# AudioMega_v101.net
KiCad netlist of a schematic drawn in EAGLE
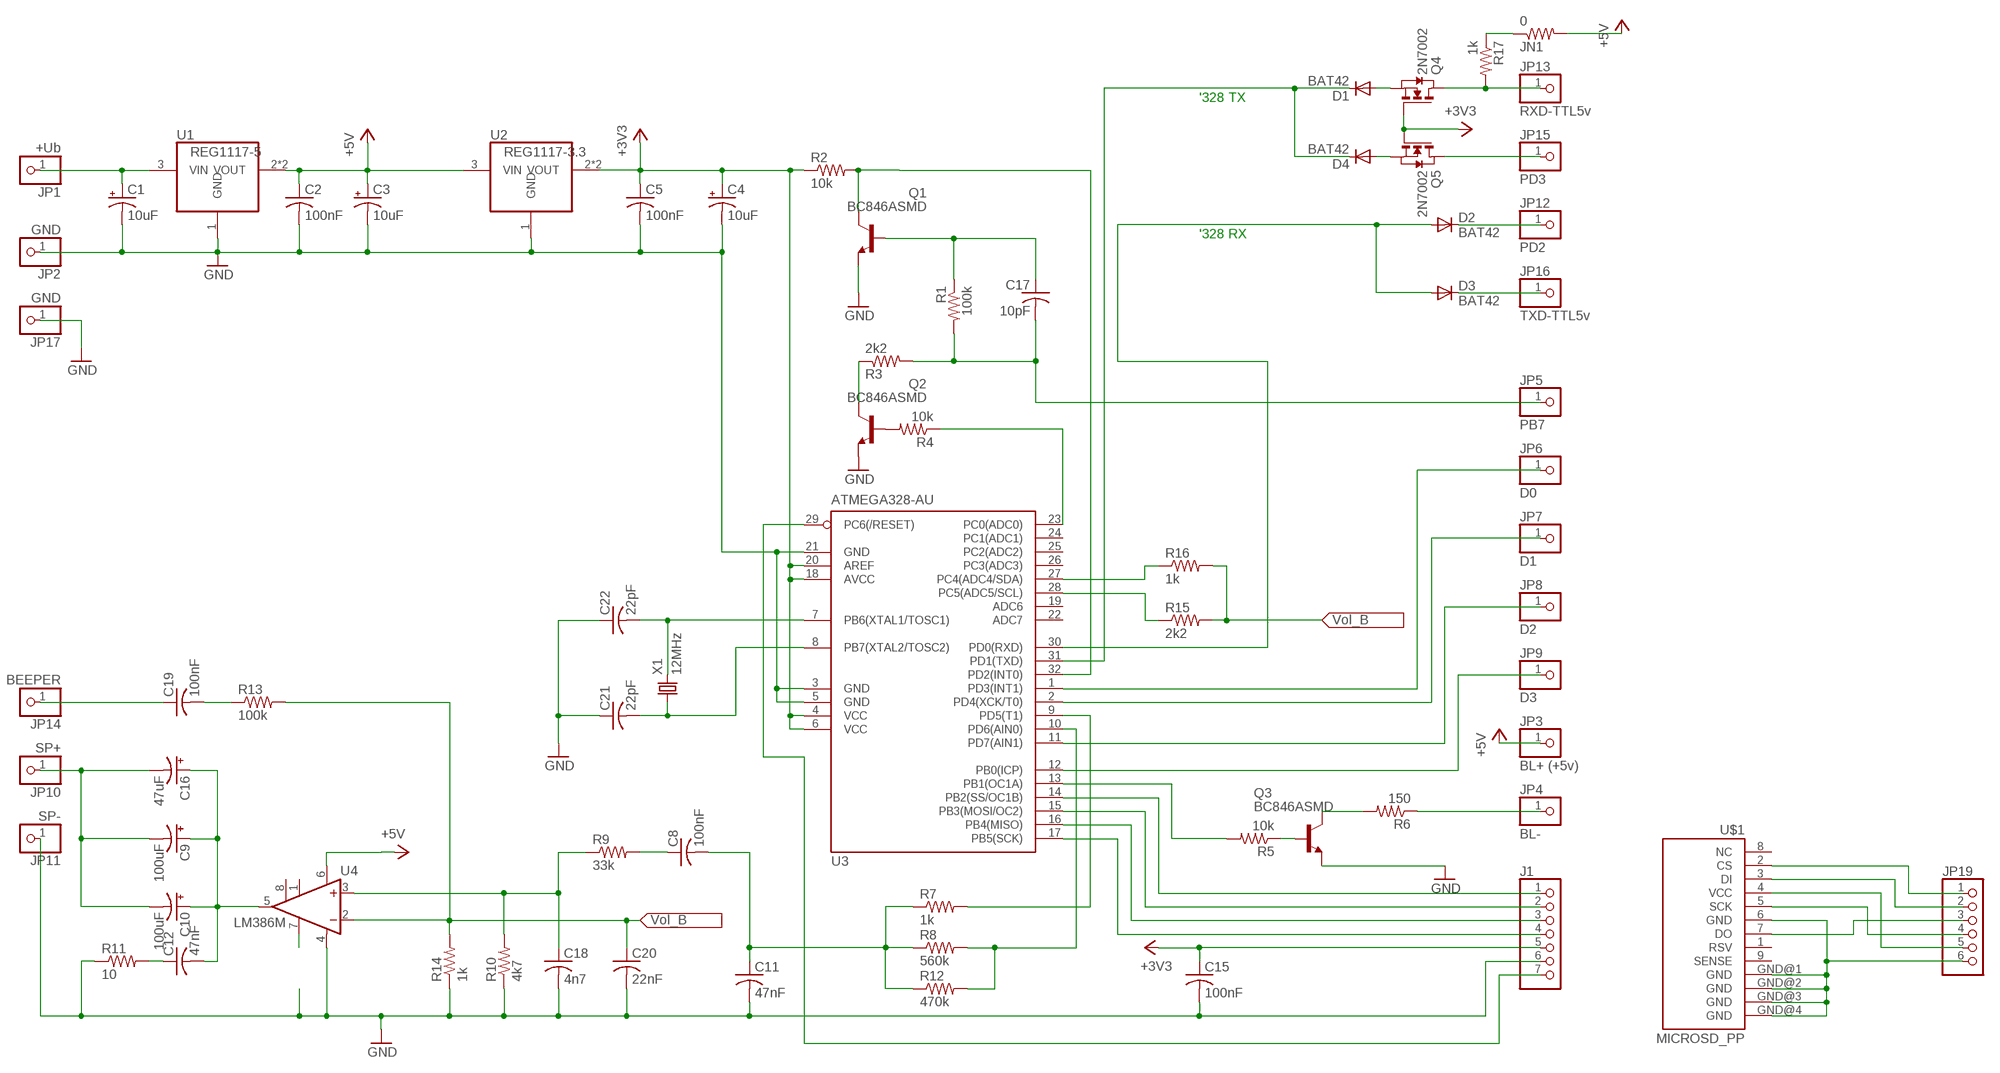
[diagram p0: schematic, sheet 1]

(export (version "E")
  (design (tool "Eeschema 10.0.6"))
  (components
    (comp (ref "C1")
      (value "10uF")
      (footprint "eagle-import:CT6032")
      (libsource (lib "eagle-import") (part "CPOL-USCT6032"))
    )
    (comp (ref "C2")
      (value "100nF")
      (footprint "eagle-import:C1206")
      (libsource (lib "eagle-import") (part "C-USC1206"))
    )
    (comp (ref "C3")
      (value "10uF")
      (footprint "eagle-import:CT6032")
      (libsource (lib "eagle-import") (part "CPOL-USCT6032"))
    )
    (comp (ref "C4")
      (value "10uF")
      (footprint "eagle-import:CT6032")
      (libsource (lib "eagle-import") (part "CPOL-USCT6032"))
    )
    (comp (ref "C5")
      (value "100nF")
      (footprint "eagle-import:C1206")
      (libsource (lib "eagle-import") (part "C-USC1206"))
    )
    (comp (ref "C8")
      (value "100nF")
      (footprint "eagle-import:C1206")
      (libsource (lib "eagle-import") (part "C-USC1206"))
    )
    (comp (ref "C9")
      (value "100uF")
      (footprint "eagle-import:CT6032")
      (libsource (lib "eagle-import") (part "CPOL-USCT6032"))
    )
    (comp (ref "C10")
      (value "100uF")
      (footprint "eagle-import:CT6032")
      (libsource (lib "eagle-import") (part "CPOL-USCT6032"))
    )
    (comp (ref "C11")
      (value "47nF")
      (footprint "eagle-import:C1206")
      (libsource (lib "eagle-import") (part "C-USC1206"))
    )
    (comp (ref "C12")
      (value "47nF")
      (footprint "eagle-import:C1206")
      (libsource (lib "eagle-import") (part "C-USC1206"))
    )
    (comp (ref "C15")
      (value "100nF")
      (footprint "eagle-import:C1206")
      (libsource (lib "eagle-import") (part "C-USC1206"))
    )
    (comp (ref "C16")
      (value "47uF")
      (footprint "eagle-import:CT6032")
      (libsource (lib "eagle-import") (part "CPOL-USCT6032"))
    )
    (comp (ref "C17")
      (value "10pF")
      (footprint "eagle-import:C1206")
      (libsource (lib "eagle-import") (part "C-USC1206"))
    )
    (comp (ref "C18")
      (value "4n7")
      (footprint "eagle-import:C1206")
      (libsource (lib "eagle-import") (part "C-USC1206"))
    )
    (comp (ref "C19")
      (value "100nF")
      (footprint "eagle-import:C1206")
      (libsource (lib "eagle-import") (part "C-USC1206"))
    )
    (comp (ref "C20")
      (value "22nF")
      (footprint "eagle-import:C1206")
      (libsource (lib "eagle-import") (part "C-USC1206"))
    )
    (comp (ref "C21")
      (value "22pF")
      (footprint "eagle-import:C1206")
      (libsource (lib "eagle-import") (part "C-USC1206"))
    )
    (comp (ref "C22")
      (value "22pF")
      (footprint "eagle-import:C1206")
      (libsource (lib "eagle-import") (part "C-USC1206"))
    )
    (comp (ref "D1")
      (value "BAT42")
      (footprint "eagle-import:SOD123")
      (libsource (lib "eagle-import") (part "DIODE-SOD123"))
    )
    (comp (ref "D2")
      (value "BAT42")
      (footprint "eagle-import:SOD123")
      (libsource (lib "eagle-import") (part "DIODE-SOD123"))
    )
    (comp (ref "D3")
      (value "BAT42")
      (footprint "eagle-import:SOD123")
      (libsource (lib "eagle-import") (part "DIODE-SOD123"))
    )
    (comp (ref "D4")
      (value "BAT42")
      (footprint "eagle-import:SOD123")
      (libsource (lib "eagle-import") (part "DIODE-SOD123"))
    )
    (comp (ref "J1")
      (value "PINHD-1X7")
      (footprint "eagle-import:1X07")
      (libsource (lib "eagle-import") (part "PINHD-1X7"))
    )
    (comp (ref "JN1")
      (value "0")
      (footprint "eagle-import:R1206")
      (libsource (lib "eagle-import") (part "R-US_R1206"))
    )
    (comp (ref "JP1")
      (value "+Ub")
      (footprint "eagle-import:1X01")
      (libsource (lib "eagle-import") (part "PINHD-1X1"))
    )
    (comp (ref "JP2")
      (value "GND")
      (footprint "eagle-import:1X01")
      (libsource (lib "eagle-import") (part "PINHD-1X1"))
    )
    (comp (ref "JP3")
      (value "BL+ (+5v)")
      (footprint "eagle-import:1X01")
      (libsource (lib "eagle-import") (part "PINHD-1X1"))
    )
    (comp (ref "JP4")
      (value "BL-")
      (footprint "eagle-import:1X01")
      (libsource (lib "eagle-import") (part "PINHD-1X1"))
    )
    (comp (ref "JP5")
      (value "PB7")
      (footprint "eagle-import:1X01")
      (libsource (lib "eagle-import") (part "PINHD-1X1"))
    )
    (comp (ref "JP6")
      (value "D0")
      (footprint "eagle-import:1X01")
      (libsource (lib "eagle-import") (part "PINHD-1X1"))
    )
    (comp (ref "JP7")
      (value "D1")
      (footprint "eagle-import:1X01")
      (libsource (lib "eagle-import") (part "PINHD-1X1"))
    )
    (comp (ref "JP8")
      (value "D2")
      (footprint "eagle-import:1X01")
      (libsource (lib "eagle-import") (part "PINHD-1X1"))
    )
    (comp (ref "JP9")
      (value "D3")
      (footprint "eagle-import:1X01")
      (libsource (lib "eagle-import") (part "PINHD-1X1"))
    )
    (comp (ref "JP10")
      (value "SP+")
      (footprint "eagle-import:1X01")
      (libsource (lib "eagle-import") (part "PINHD-1X1"))
    )
    (comp (ref "JP11")
      (value "SP-")
      (footprint "eagle-import:1X01")
      (libsource (lib "eagle-import") (part "PINHD-1X1"))
    )
    (comp (ref "JP12")
      (value "PD2")
      (footprint "eagle-import:1X01")
      (libsource (lib "eagle-import") (part "PINHD-1X1"))
    )
    (comp (ref "JP13")
      (value "RXD-TTL5v")
      (footprint "eagle-import:1X01")
      (libsource (lib "eagle-import") (part "PINHD-1X1"))
    )
    (comp (ref "JP14")
      (value "BEEPER")
      (footprint "eagle-import:1X01")
      (libsource (lib "eagle-import") (part "PINHD-1X1"))
    )
    (comp (ref "JP15")
      (value "PD3")
      (footprint "eagle-import:1X01")
      (libsource (lib "eagle-import") (part "PINHD-1X1"))
    )
    (comp (ref "JP16")
      (value "TXD-TTL5v")
      (footprint "eagle-import:1X01")
      (libsource (lib "eagle-import") (part "PINHD-1X1"))
    )
    (comp (ref "JP17")
      (value "GND")
      (footprint "eagle-import:1X01")
      (libsource (lib "eagle-import") (part "PINHD-1X1"))
    )
    (comp (ref "JP19")
      (value "PINHD-1X6")
      (footprint "eagle-import:1X06")
      (libsource (lib "eagle-import") (part "PINHD-1X6"))
    )
    (comp (ref "Q1")
      (value "BC846ASMD")
      (footprint "eagle-import:SOT23")
      (libsource (lib "eagle-import") (part "BC846SMDA"))
    )
    (comp (ref "Q2")
      (value "BC846ASMD")
      (footprint "eagle-import:SOT23")
      (libsource (lib "eagle-import") (part "BC846SMDA"))
    )
    (comp (ref "Q3")
      (value "BC846ASMD")
      (footprint "eagle-import:SOT23")
      (libsource (lib "eagle-import") (part "BC846SMDA"))
    )
    (comp (ref "Q4")
      (value "2N7002")
      (footprint "eagle-import:SOT-23")
      (libsource (lib "eagle-import") (part "NMOSSOT23"))
    )
    (comp (ref "Q5")
      (value "2N7002")
      (footprint "eagle-import:SOT-23")
      (fields (field (name "OC_FARNELL") "unknown") (field (name "OC_NEWARK") "unknown"))
      (libsource (lib "eagle-import") (part "NMOSSOT23"))
    )
    (comp (ref "R1")
      (value "100k")
      (footprint "eagle-import:R1206")
      (libsource (lib "eagle-import") (part "R-US_R1206"))
    )
    (comp (ref "R2")
      (value "10k")
      (footprint "eagle-import:R1206")
      (libsource (lib "eagle-import") (part "R-US_R1206"))
    )
    (comp (ref "R3")
      (value "2k2")
      (footprint "eagle-import:R1206")
      (libsource (lib "eagle-import") (part "R-US_R1206"))
    )
    (comp (ref "R4")
      (value "10k")
      (footprint "eagle-import:R1206")
      (libsource (lib "eagle-import") (part "R-US_R1206"))
    )
    (comp (ref "R5")
      (value "10k")
      (footprint "eagle-import:R1206")
      (libsource (lib "eagle-import") (part "R-US_R1206"))
    )
    (comp (ref "R6")
      (value "150")
      (footprint "eagle-import:R1206")
      (libsource (lib "eagle-import") (part "R-US_R1206"))
    )
    (comp (ref "R7")
      (value "1k")
      (footprint "eagle-import:R1206")
      (libsource (lib "eagle-import") (part "R-US_R1206"))
    )
    (comp (ref "R8")
      (value "560k")
      (footprint "eagle-import:R1206")
      (libsource (lib "eagle-import") (part "R-US_R1206"))
    )
    (comp (ref "R9")
      (value "33k")
      (footprint "eagle-import:R1206")
      (libsource (lib "eagle-import") (part "R-US_R1206"))
    )
    (comp (ref "R10")
      (value "4k7")
      (footprint "eagle-import:R1206")
      (libsource (lib "eagle-import") (part "R-US_R1206"))
    )
    (comp (ref "R11")
      (value "10")
      (footprint "eagle-import:R1206")
      (libsource (lib "eagle-import") (part "R-US_R1206"))
    )
    (comp (ref "R12")
      (value "470k")
      (footprint "eagle-import:R1206")
      (libsource (lib "eagle-import") (part "R-US_R1206"))
    )
    (comp (ref "R13")
      (value "100k")
      (footprint "eagle-import:R1206")
      (libsource (lib "eagle-import") (part "R-US_R1206"))
    )
    (comp (ref "R14")
      (value "1k")
      (footprint "eagle-import:R1206")
      (libsource (lib "eagle-import") (part "R-US_R1206"))
    )
    (comp (ref "R15")
      (value "2k2")
      (footprint "eagle-import:R1206")
      (libsource (lib "eagle-import") (part "R-US_R1206"))
    )
    (comp (ref "R16")
      (value "1k")
      (footprint "eagle-import:R1206")
      (libsource (lib "eagle-import") (part "R-US_R1206"))
    )
    (comp (ref "R17")
      (value "1k")
      (footprint "eagle-import:R1206")
      (libsource (lib "eagle-import") (part "R-US_R1206"))
    )
    (comp (ref "U$1")
      (value "MICROSD_PP")
      (footprint "eagle-import:MICROSD_PP")
      (libsource (lib "eagle-import") (part "MICROSD_PP"))
    )
    (comp (ref "U1")
      (value "REG1117-5")
      (footprint "eagle-import:SOT223")
      (fields (field (name "MPN") "REG1117"))
      (libsource (lib "eagle-import") (part "REG1117"))
    )
    (comp (ref "U2")
      (value "REG1117-3.3")
      (footprint "eagle-import:SOT223")
      (fields (field (name "MPN") "REG1117"))
      (libsource (lib "eagle-import") (part "REG1117"))
    )
    (comp (ref "U3")
      (value "ATMEGA328-AU")
      (footprint "eagle-import:TQFP32-08")
      (fields (field (name "MPN") "ATMEGA8-16AU"))
      (libsource (lib "eagle-import") (part "MEGA8-AI"))
    )
    (comp (ref "U4")
      (value "LM386M")
      (footprint "eagle-import:SO08")
      (libsource (lib "eagle-import") (part "LM386?-M1"))
    )
    (comp (ref "X1")
      (value "12MHz")
      (footprint "eagle-import:HC49UP")
      (libsource (lib "eagle-import") (part "CRYSTALHC49UP"))
    )
  )
  (nets
    (net (code "1") (name "+3V3") (class "Default")
      (node (ref "C15") (pin "1") (pinfunction "1_1") (pintype "passive"))
      (node (ref "C4") (pin "+") (pinfunction "+_+") (pintype "passive"))
      (node (ref "C5") (pin "1") (pinfunction "1_1") (pintype "passive"))
      (node (ref "J1") (pin "5") (pinfunction "5_5") (pintype "passive"))
      (node (ref "Q4") (pin "3") (pinfunction "G_3") (pintype "passive"))
      (node (ref "Q5") (pin "3") (pinfunction "G_3") (pintype "passive"))
      (node (ref "R2") (pin "1") (pinfunction "1_1") (pintype "passive"))
      (node (ref "U2") (pin "2") (pinfunction "VOUT_2") (pintype "output"))
      (node (ref "U2") (pin "4") (pinfunction "VOUT_4") (pintype "output"))
      (node (ref "U3") (pin "18") (pinfunction "AVCC_18") (pintype "power_in"))
      (node (ref "U3") (pin "20") (pinfunction "AREF_20") (pintype "passive"))
      (node (ref "U3") (pin "4") (pinfunction "VCC_4") (pintype "power_in"))
      (node (ref "U3") (pin "6") (pinfunction "VCC_6") (pintype "power_in"))
    )
    (net (code "2") (name "+5V") (class "Default")
      (node (ref "C2") (pin "1") (pinfunction "1_1") (pintype "passive"))
      (node (ref "C3") (pin "+") (pinfunction "+_+") (pintype "passive"))
      (node (ref "JN1") (pin "2") (pinfunction "2_2") (pintype "passive"))
      (node (ref "JP3") (pin "1") (pinfunction "1_1") (pintype "passive"))
      (node (ref "U1") (pin "2") (pinfunction "VOUT_2") (pintype "output"))
      (node (ref "U1") (pin "4") (pinfunction "VOUT_4") (pintype "output"))
      (node (ref "U2") (pin "3") (pinfunction "VIN_3") (pintype "input"))
      (node (ref "U4") (pin "6") (pinfunction "VS_6") (pintype "power_in"))
    )
    (net (code "3") (name "/VOL_B") (class "Default")
      (node (ref "C20") (pin "1") (pinfunction "1_1") (pintype "passive"))
      (node (ref "R13") (pin "2") (pinfunction "2_2") (pintype "passive"))
      (node (ref "R14") (pin "2") (pinfunction "2_2") (pintype "passive"))
      (node (ref "R15") (pin "2") (pinfunction "2_2") (pintype "passive"))
      (node (ref "R16") (pin "2") (pinfunction "2_2") (pintype "passive"))
      (node (ref "U4") (pin "2") (pinfunction "-IN_2") (pintype "input"))
    )
    (net (code "4") (name "GND") (class "Default")
      (node (ref "C1") (pin "-") (pinfunction "-_-") (pintype "passive"))
      (node (ref "C11") (pin "2") (pinfunction "2_2") (pintype "passive"))
      (node (ref "C15") (pin "2") (pinfunction "2_2") (pintype "passive"))
      (node (ref "C18") (pin "2") (pinfunction "2_2") (pintype "passive"))
      (node (ref "C2") (pin "2") (pinfunction "2_2") (pintype "passive"))
      (node (ref "C20") (pin "2") (pinfunction "2_2") (pintype "passive"))
      (node (ref "C21") (pin "1") (pinfunction "1_1") (pintype "passive"))
      (node (ref "C22") (pin "1") (pinfunction "1_1") (pintype "passive"))
      (node (ref "C3") (pin "-") (pinfunction "-_-") (pintype "passive"))
      (node (ref "C4") (pin "-") (pinfunction "-_-") (pintype "passive"))
      (node (ref "C5") (pin "2") (pinfunction "2_2") (pintype "passive"))
      (node (ref "J1") (pin "6") (pinfunction "6_6") (pintype "passive"))
      (node (ref "JP11") (pin "1") (pinfunction "1_1") (pintype "passive"))
      (node (ref "JP17") (pin "1") (pinfunction "1_1") (pintype "passive"))
      (node (ref "JP2") (pin "1") (pinfunction "1_1") (pintype "passive"))
      (node (ref "Q1") (pin "2") (pinfunction "E_2") (pintype "passive"))
      (node (ref "Q2") (pin "2") (pinfunction "E_2") (pintype "passive"))
      (node (ref "Q3") (pin "2") (pinfunction "E_2") (pintype "passive"))
      (node (ref "R10") (pin "1") (pinfunction "1_1") (pintype "passive"))
      (node (ref "R11") (pin "1") (pinfunction "1_1") (pintype "passive"))
      (node (ref "R14") (pin "1") (pinfunction "1_1") (pintype "passive"))
      (node (ref "U1") (pin "1") (pinfunction "GND_1") (pintype "power_in"))
      (node (ref "U2") (pin "1") (pinfunction "GND_1") (pintype "power_in"))
      (node (ref "U3") (pin "21") (pinfunction "GND_21") (pintype "power_in"))
      (node (ref "U3") (pin "3") (pinfunction "GND_3") (pintype "power_in"))
      (node (ref "U3") (pin "5") (pinfunction "GND_5") (pintype "power_in"))
      (node (ref "U4") (pin "4") (pinfunction "GND_4") (pintype "power_in"))
    )
    (net (code "5") (name "Net-(C8-Pad1)") (class "Default")
      (node (ref "C8") (pin "1") (pinfunction "1_1") (pintype "passive"))
      (node (ref "R9") (pin "2") (pinfunction "2_2") (pintype "passive"))
    )
    (net (code "6") (name "Net-(C10-Pad-)") (class "Default")
      (node (ref "C10") (pin "-") (pinfunction "-_-") (pintype "passive"))
      (node (ref "C16") (pin "-") (pinfunction "-_-") (pintype "passive"))
      (node (ref "C9") (pin "-") (pinfunction "-_-") (pintype "passive"))
      (node (ref "JP10") (pin "1") (pinfunction "1_1") (pintype "passive"))
    )
    (net (code "7") (name "Net-(C11-Pad1)") (class "Default")
      (node (ref "C11") (pin "1") (pinfunction "1_1") (pintype "passive"))
      (node (ref "C8") (pin "2") (pinfunction "2_2") (pintype "passive"))
      (node (ref "R12") (pin "1") (pinfunction "1_1") (pintype "passive"))
      (node (ref "R7") (pin "1") (pinfunction "1_1") (pintype "passive"))
      (node (ref "R8") (pin "1") (pinfunction "1_1") (pintype "passive"))
    )
    (net (code "8") (name "Net-(C12-Pad1)") (class "Default")
      (node (ref "C12") (pin "1") (pinfunction "1_1") (pintype "passive"))
      (node (ref "R11") (pin "2") (pinfunction "2_2") (pintype "passive"))
    )
    (net (code "9") (name "Net-(C17-Pad2)") (class "Default")
      (node (ref "C17") (pin "2") (pinfunction "2_2") (pintype "passive"))
      (node (ref "JP5") (pin "1") (pinfunction "1_1") (pintype "passive"))
      (node (ref "R1") (pin "2") (pinfunction "2_2") (pintype "passive"))
      (node (ref "R3") (pin "2") (pinfunction "2_2") (pintype "passive"))
    )
    (net (code "10") (name "Net-(C19-Pad1)") (class "Default")
      (node (ref "C19") (pin "1") (pinfunction "1_1") (pintype "passive"))
      (node (ref "JP14") (pin "1") (pinfunction "1_1") (pintype "passive"))
    )
    (net (code "11") (name "Net-(C19-Pad2)") (class "Default")
      (node (ref "C19") (pin "2") (pinfunction "2_2") (pintype "passive"))
      (node (ref "R13") (pin "1") (pinfunction "1_1") (pintype "passive"))
    )
    (net (code "12") (name "Net-(D2-PadC)") (class "Default")
      (node (ref "D2") (pin "C") (pinfunction "C_C") (pintype "passive"))
      (node (ref "JP12") (pin "1") (pinfunction "1_1") (pintype "passive"))
    )
    (net (code "13") (name "Net-(D3-PadC)") (class "Default")
      (node (ref "D3") (pin "C") (pinfunction "C_C") (pintype "passive"))
      (node (ref "JP16") (pin "1") (pinfunction "1_1") (pintype "passive"))
    )
    (net (code "14") (name "Net-(JN1-Pad1)") (class "Default")
      (node (ref "JN1") (pin "1") (pinfunction "1_1") (pintype "passive"))
      (node (ref "R17") (pin "1") (pinfunction "1_1") (pintype "passive"))
    )
    (net (code "15") (name "Net-(JP4-Pad1)") (class "Default")
      (node (ref "JP4") (pin "1") (pinfunction "1_1") (pintype "passive"))
      (node (ref "R6") (pin "1") (pinfunction "1_1") (pintype "passive"))
    )
    (net (code "16") (name "Net-(JP19-Pad6)") (class "Default")
      (node (ref "JP19") (pin "6") (pinfunction "6_6") (pintype "passive"))
      (node (ref "U$1") (pin "6") (pinfunction "GND_6") (pintype "bidirectional"))
      (node (ref "U$1") (pin "GND@1") (pinfunction "GND_GND@1") (pintype "bidirectional"))
      (node (ref "U$1") (pin "GND@2") (pinfunction "GND_GND@2") (pintype "bidirectional"))
      (node (ref "U$1") (pin "GND@3") (pinfunction "GND_GND@3") (pintype "bidirectional"))
      (node (ref "U$1") (pin "GND@4") (pinfunction "GND_GND@4") (pintype "bidirectional"))
    )
    (net (code "17") (name "Net-(Q1-B)") (class "Default")
      (node (ref "C17") (pin "1") (pinfunction "1_1") (pintype "passive"))
      (node (ref "Q1") (pin "1") (pinfunction "B_1") (pintype "passive"))
      (node (ref "R1") (pin "1") (pinfunction "1_1") (pintype "passive"))
    )
    (net (code "18") (name "Net-(Q1-C)") (class "Default")
      (node (ref "Q1") (pin "3") (pinfunction "C_3") (pintype "passive"))
      (node (ref "R2") (pin "2") (pinfunction "2_2") (pintype "passive"))
      (node (ref "U3") (pin "32") (pinfunction "PD2(INT0)_32") (pintype "bidirectional"))
    )
    (net (code "19") (name "Net-(Q2-B)") (class "Default")
      (node (ref "Q2") (pin "1") (pinfunction "B_1") (pintype "passive"))
      (node (ref "R4") (pin "2") (pinfunction "2_2") (pintype "passive"))
    )
    (net (code "20") (name "Net-(Q2-C)") (class "Default")
      (node (ref "Q2") (pin "3") (pinfunction "C_3") (pintype "passive"))
      (node (ref "R3") (pin "1") (pinfunction "1_1") (pintype "passive"))
    )
    (net (code "21") (name "Net-(Q3-B)") (class "Default")
      (node (ref "Q3") (pin "1") (pinfunction "B_1") (pintype "passive"))
      (node (ref "R5") (pin "1") (pinfunction "1_1") (pintype "passive"))
    )
    (net (code "22") (name "Net-(Q3-C)") (class "Default")
      (node (ref "Q3") (pin "3") (pinfunction "C_3") (pintype "passive"))
      (node (ref "R6") (pin "2") (pinfunction "2_2") (pintype "passive"))
    )
    (net (code "23") (name "Net-(Q4-D)") (class "Default")
      (node (ref "JP13") (pin "1") (pinfunction "1_1") (pintype "passive"))
      (node (ref "Q4") (pin "1") (pinfunction "D_1") (pintype "passive"))
      (node (ref "R17") (pin "2") (pinfunction "2_2") (pintype "passive"))
    )
    (net (code "24") (name "Net-(Q4-S)") (class "Default")
      (node (ref "D1") (pin "A") (pinfunction "A_A") (pintype "passive"))
      (node (ref "Q4") (pin "2") (pinfunction "S_2") (pintype "passive"))
    )
    (net (code "25") (name "Net-(Q5-D)") (class "Default")
      (node (ref "JP15") (pin "1") (pinfunction "1_1") (pintype "passive"))
      (node (ref "Q5") (pin "1") (pinfunction "D_1") (pintype "passive"))
    )
    (net (code "26") (name "Net-(Q5-S)") (class "Default")
      (node (ref "D4") (pin "A") (pinfunction "A_A") (pintype "passive"))
      (node (ref "Q5") (pin "2") (pinfunction "S_2") (pintype "passive"))
    )
    (net (code "27") (name "Net-(U$1-CS)") (class "Default")
      (node (ref "JP19") (pin "1") (pinfunction "1_1") (pintype "passive"))
      (node (ref "U$1") (pin "2") (pinfunction "CS_2") (pintype "bidirectional"))
    )
    (net (code "28") (name "Net-(U$1-DI)") (class "Default")
      (node (ref "JP19") (pin "2") (pinfunction "2_2") (pintype "passive"))
      (node (ref "U$1") (pin "3") (pinfunction "DI_3") (pintype "bidirectional"))
    )
    (net (code "29") (name "Net-(U$1-DO)") (class "Default")
      (node (ref "JP19") (pin "3") (pinfunction "3_3") (pintype "passive"))
      (node (ref "U$1") (pin "7") (pinfunction "DO_7") (pintype "bidirectional"))
    )
    (net (code "30") (name "Net-(U$1-SCK)") (class "Default")
      (node (ref "JP19") (pin "4") (pinfunction "4_4") (pintype "passive"))
      (node (ref "U$1") (pin "5") (pinfunction "SCK_5") (pintype "bidirectional"))
    )
    (net (code "31") (name "Net-(U$1-VCC)") (class "Default")
      (node (ref "JP19") (pin "5") (pinfunction "5_5") (pintype "passive"))
      (node (ref "U$1") (pin "4") (pinfunction "VCC_4") (pintype "bidirectional"))
    )
    (net (code "32") (name "Net-(U1-VIN)") (class "Default")
      (node (ref "C1") (pin "+") (pinfunction "+_+") (pintype "passive"))
      (node (ref "JP1") (pin "1") (pinfunction "1_1") (pintype "passive"))
      (node (ref "U1") (pin "3") (pinfunction "VIN_3") (pintype "input"))
    )
    (net (code "33") (name "Net-(U3-PB0(ICP))") (class "Default")
      (node (ref "JP9") (pin "1") (pinfunction "1_1") (pintype "passive"))
      (node (ref "U3") (pin "12") (pinfunction "PB0(ICP)_12") (pintype "bidirectional"))
    )
    (net (code "34") (name "Net-(U3-PB1(OC1A))") (class "Default")
      (node (ref "R5") (pin "2") (pinfunction "2_2") (pintype "passive"))
      (node (ref "U3") (pin "13") (pinfunction "PB1(OC1A)_13") (pintype "bidirectional"))
    )
    (net (code "35") (name "Net-(U3-PB2(SS{slash}OC1B))") (class "Default")
      (node (ref "J1") (pin "1") (pinfunction "1_1") (pintype "passive"))
      (node (ref "U3") (pin "14") (pinfunction "PB2(SS/OC1B)_14") (pintype "bidirectional"))
    )
    (net (code "36") (name "Net-(U3-PB3(MOSI{slash}OC2))") (class "Default")
      (node (ref "J1") (pin "2") (pinfunction "2_2") (pintype "passive"))
      (node (ref "U3") (pin "15") (pinfunction "PB3(MOSI/OC2)_15") (pintype "bidirectional"))
    )
    (net (code "37") (name "Net-(U3-PB4(MISO))") (class "Default")
      (node (ref "J1") (pin "3") (pinfunction "3_3") (pintype "passive"))
      (node (ref "U3") (pin "16") (pinfunction "PB4(MISO)_16") (pintype "bidirectional"))
    )
    (net (code "38") (name "Net-(U3-PB5(SCK))") (class "Default")
      (node (ref "J1") (pin "4") (pinfunction "4_4") (pintype "passive"))
      (node (ref "U3") (pin "17") (pinfunction "PB5(SCK)_17") (pintype "bidirectional"))
    )
    (net (code "39") (name "Net-(U3-PB6(XTAL1{slash}TOSC1))") (class "Default")
      (node (ref "C22") (pin "2") (pinfunction "2_2") (pintype "passive"))
      (node (ref "U3") (pin "7") (pinfunction "PB6(XTAL1/TOSC1)_7") (pintype "bidirectional"))
      (node (ref "X1") (pin "2") (pinfunction "2_2") (pintype "passive"))
    )
    (net (code "40") (name "Net-(U3-PB7(XTAL2{slash}TOSC2))") (class "Default")
      (node (ref "C21") (pin "2") (pinfunction "2_2") (pintype "passive"))
      (node (ref "U3") (pin "8") (pinfunction "PB7(XTAL2/TOSC2)_8") (pintype "bidirectional"))
      (node (ref "X1") (pin "1") (pinfunction "1_1") (pintype "passive"))
    )
    (net (code "41") (name "Net-(U3-PC0(ADC0))") (class "Default")
      (node (ref "R4") (pin "1") (pinfunction "1_1") (pintype "passive"))
      (node (ref "U3") (pin "23") (pinfunction "PC0(ADC0)_23") (pintype "bidirectional"))
    )
    (net (code "42") (name "Net-(U3-PC4(ADC4{slash}SDA))") (class "Default")
      (node (ref "R16") (pin "1") (pinfunction "1_1") (pintype "passive"))
      (node (ref "U3") (pin "27") (pinfunction "PC4(ADC4/SDA)_27") (pintype "bidirectional"))
    )
    (net (code "43") (name "Net-(U3-PC5(ADC5{slash}SCL))") (class "Default")
      (node (ref "R15") (pin "1") (pinfunction "1_1") (pintype "passive"))
      (node (ref "U3") (pin "28") (pinfunction "PC5(ADC5/SCL)_28") (pintype "bidirectional"))
    )
    (net (code "44") (name "Net-(U3-PC6({slash}RESET))") (class "Default")
      (node (ref "J1") (pin "7") (pinfunction "7_7") (pintype "passive"))
      (node (ref "U3") (pin "29") (pinfunction "PC6(/RESET)_29") (pintype "bidirectional"))
    )
    (net (code "45") (name "Net-(U3-PD0(RXD))") (class "Default")
      (node (ref "D2") (pin "A") (pinfunction "A_A") (pintype "passive"))
      (node (ref "D3") (pin "A") (pinfunction "A_A") (pintype "passive"))
      (node (ref "U3") (pin "30") (pinfunction "PD0(RXD)_30") (pintype "bidirectional"))
    )
    (net (code "46") (name "Net-(U3-PD1(TXD))") (class "Default")
      (node (ref "D1") (pin "C") (pinfunction "C_C") (pintype "passive"))
      (node (ref "D4") (pin "C") (pinfunction "C_C") (pintype "passive"))
      (node (ref "U3") (pin "31") (pinfunction "PD1(TXD)_31") (pintype "bidirectional"))
    )
    (net (code "47") (name "Net-(U3-PD3(INT1))") (class "Default")
      (node (ref "JP6") (pin "1") (pinfunction "1_1") (pintype "passive"))
      (node (ref "U3") (pin "1") (pinfunction "PD3(INT1)_1") (pintype "bidirectional"))
    )
    (net (code "48") (name "Net-(U3-PD4(XCK{slash}T0))") (class "Default")
      (node (ref "JP7") (pin "1") (pinfunction "1_1") (pintype "passive"))
      (node (ref "U3") (pin "2") (pinfunction "PD4(XCK/T0)_2") (pintype "bidirectional"))
    )
    (net (code "49") (name "Net-(U3-PD5(T1))") (class "Default")
      (node (ref "R7") (pin "2") (pinfunction "2_2") (pintype "passive"))
      (node (ref "U3") (pin "9") (pinfunction "PD5(T1)_9") (pintype "bidirectional"))
    )
    (net (code "50") (name "Net-(U3-PD6(AIN0))") (class "Default")
      (node (ref "R12") (pin "2") (pinfunction "2_2") (pintype "passive"))
      (node (ref "R8") (pin "2") (pinfunction "2_2") (pintype "passive"))
      (node (ref "U3") (pin "10") (pinfunction "PD6(AIN0)_10") (pintype "bidirectional"))
    )
    (net (code "51") (name "Net-(U3-PD7(AIN1))") (class "Default")
      (node (ref "JP8") (pin "1") (pinfunction "1_1") (pintype "passive"))
      (node (ref "U3") (pin "11") (pinfunction "PD7(AIN1)_11") (pintype "bidirectional"))
    )
    (net (code "52") (name "Net-(U4-+IN)") (class "Default")
      (node (ref "C18") (pin "1") (pinfunction "1_1") (pintype "passive"))
      (node (ref "R10") (pin "2") (pinfunction "2_2") (pintype "passive"))
      (node (ref "R9") (pin "1") (pinfunction "1_1") (pintype "passive"))
      (node (ref "U4") (pin "3") (pinfunction "+IN_3") (pintype "input"))
    )
    (net (code "53") (name "Net-(U4-OUT)") (class "Default")
      (node (ref "C10") (pin "+") (pinfunction "+_+") (pintype "passive"))
      (node (ref "C12") (pin "2") (pinfunction "2_2") (pintype "passive"))
      (node (ref "C16") (pin "+") (pinfunction "+_+") (pintype "passive"))
      (node (ref "C9") (pin "+") (pinfunction "+_+") (pintype "passive"))
      (node (ref "U4") (pin "5") (pinfunction "OUT_5") (pintype "output"))
    )
    (net (code "54") (name "unconnected-(U$1-NC-Pad8)") (class "Default")
      (node (ref "U$1") (pin "8") (pinfunction "NC_8") (pintype "bidirectional"))
    )
    (net (code "55") (name "unconnected-(U$1-RSV-Pad1)") (class "Default")
      (node (ref "U$1") (pin "1") (pinfunction "RSV_1") (pintype "bidirectional"))
    )
    (net (code "56") (name "unconnected-(U$1-SENSE-Pad9)") (class "Default")
      (node (ref "U$1") (pin "9") (pinfunction "SENSE_9") (pintype "bidirectional"))
    )
    (net (code "57") (name "unconnected-(U3-ADC6-Pad19)") (class "Default")
      (node (ref "U3") (pin "19") (pinfunction "ADC6_19") (pintype "bidirectional"))
    )
    (net (code "58") (name "unconnected-(U3-ADC7-Pad22)") (class "Default")
      (node (ref "U3") (pin "22") (pinfunction "ADC7_22") (pintype "bidirectional"))
    )
    (net (code "59") (name "unconnected-(U3-PC1(ADC1)-Pad24)") (class "Default")
      (node (ref "U3") (pin "24") (pinfunction "PC1(ADC1)_24") (pintype "bidirectional"))
    )
    (net (code "60") (name "unconnected-(U3-PC2(ADC2)-Pad25)") (class "Default")
      (node (ref "U3") (pin "25") (pinfunction "PC2(ADC2)_25") (pintype "bidirectional"))
    )
    (net (code "61") (name "unconnected-(U3-PC3(ADC3)-Pad26)") (class "Default")
      (node (ref "U3") (pin "26") (pinfunction "PC3(ADC3)_26") (pintype "bidirectional"))
    )
    (net (code "62") (name "unconnected-(U4-BYPASS-Pad7)") (class "Default")
      (node (ref "U4") (pin "7") (pinfunction "BYPASS_7") (pintype "passive"))
    )
    (net (code "63") (name "unconnected-(U4-GAIN-Pad1)") (class "Default")
      (node (ref "U4") (pin "1") (pinfunction "GAIN_1") (pintype "passive"))
    )
    (net (code "64") (name "unconnected-(U4-GAIN-Pad8)") (class "Default")
      (node (ref "U4") (pin "8") (pinfunction "GAIN_8") (pintype "passive"))
    )
  )
)
